# User_Interface.net
KiCad netlist of a schematic drawn in Altium Designer
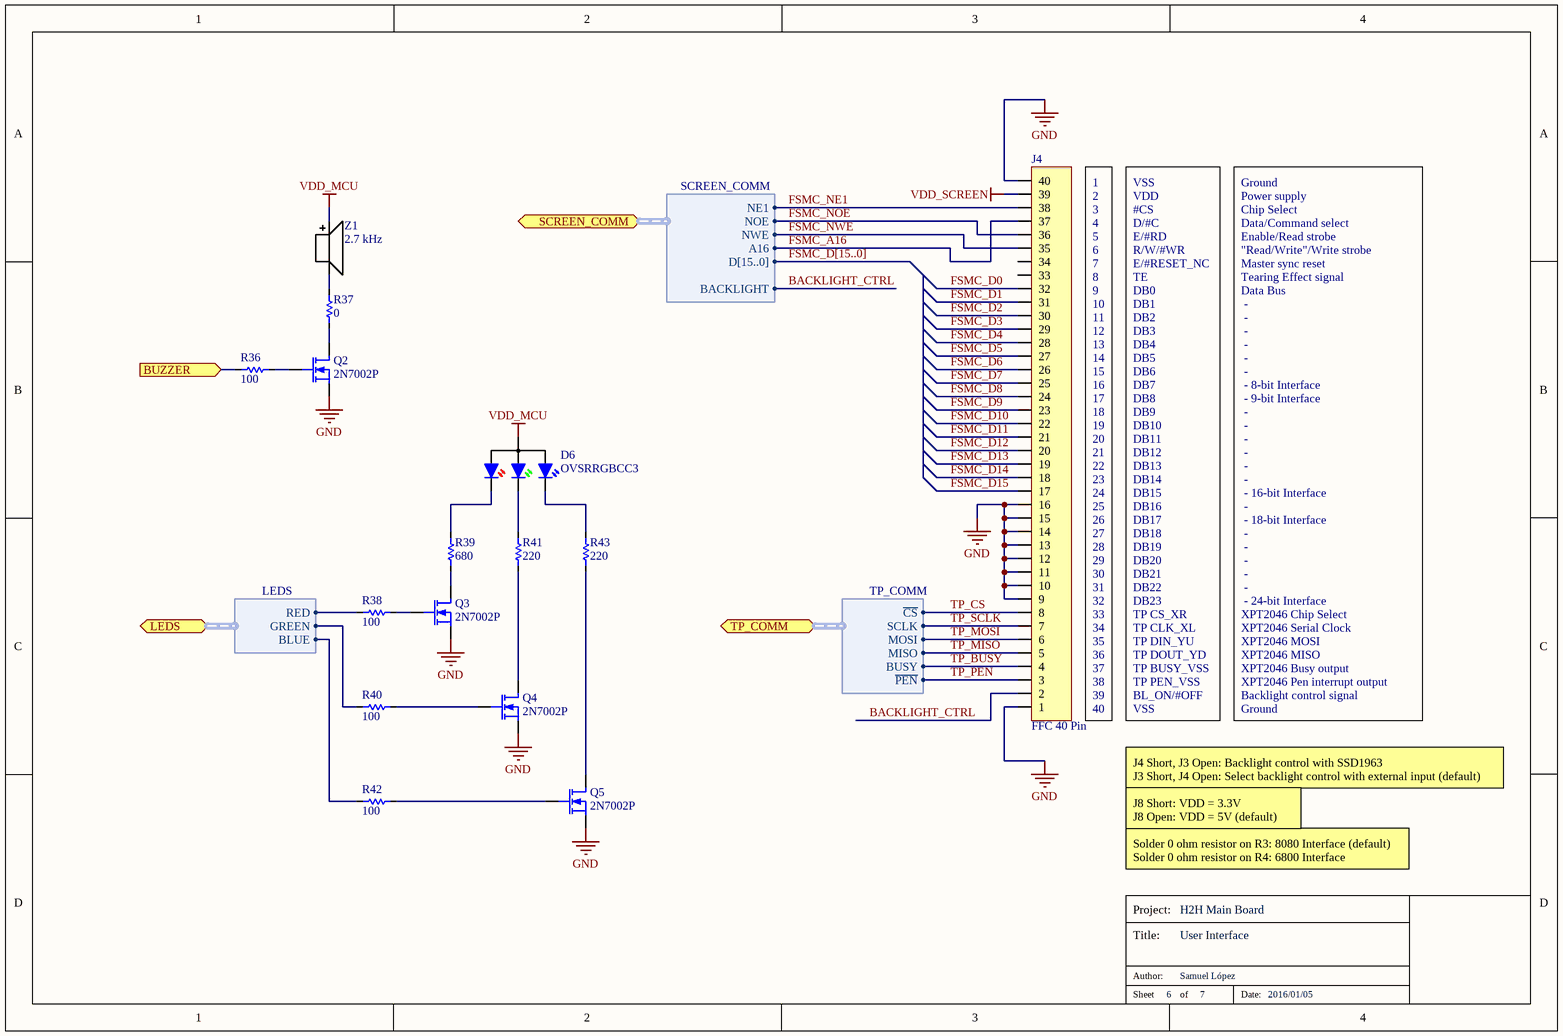
[diagram p0: User Interface.SchDoc]

(export (version "E")
  (design (tool "Eeschema 10.0.6"))
  (components
    (comp (ref "D6")
      (value "OVSRRGBCC3")
      (footprint "OVSRRGBCC3/SIDE")
      (description "LED - RGB, Top/Side-emmiting")
      (libsource (lib "H2H") (part "OVSRRGBCC3"))
    )
    (comp (ref "J4")
      (value "FFC 40 Pin")
      (footprint "ER-CON40HB-2")
      (description "Conn - FFC/FPC, 40 Pin, 1.0mm Pitch, ZIF")
      (libsource (lib "Conn") (part "ER-CON40HB-2"))
    )
    (comp (ref "Q2")
      (value "2N7002P")
      (footprint "2N7002P")
      (description "Transistor - MOSFET, N-Channel, 60V, 300mA")
      (libsource (lib "H2H") (part "2N7002P"))
    )
    (comp (ref "Q3")
      (value "2N7002P")
      (footprint "2N7002P")
      (description "Transistor - MOSFET, N-Channel, 60V, 300mA")
      (libsource (lib "H2H") (part "2N7002P"))
    )
    (comp (ref "Q4")
      (value "2N7002P")
      (footprint "2N7002P")
      (description "Transistor - MOSFET, N-Channel, 60V, 300mA")
      (libsource (lib "H2H") (part "2N7002P"))
    )
    (comp (ref "Q5")
      (value "2N7002P")
      (footprint "2N7002P")
      (description "Transistor - MOSFET, N-Channel, 60V, 300mA")
      (libsource (lib "H2H") (part "2N7002P"))
    )
    (comp (ref "R36")
      (value "100")
      (footprint "R0603")
      (description "Resistor")
      (libsource (lib "Misc") (part "Resistor"))
    )
    (comp (ref "R37")
      (value "0")
      (footprint "R0603")
      (description "Resistor")
      (libsource (lib "Misc") (part "Resistor"))
    )
    (comp (ref "R38")
      (value "100")
      (footprint "R0603")
      (description "Resistor")
      (libsource (lib "Misc") (part "Resistor"))
    )
    (comp (ref "R39")
      (value "680")
      (footprint "R0603")
      (description "Resistor")
      (libsource (lib "Misc") (part "Resistor"))
    )
    (comp (ref "R40")
      (value "100")
      (footprint "R0603")
      (description "Resistor")
      (libsource (lib "Misc") (part "Resistor"))
    )
    (comp (ref "R41")
      (value "220")
      (footprint "R0603")
      (description "Resistor")
      (libsource (lib "Misc") (part "Resistor"))
    )
    (comp (ref "R42")
      (value "100")
      (footprint "R0603")
      (description "Resistor")
      (libsource (lib "Misc") (part "Resistor"))
    )
    (comp (ref "R43")
      (value "220")
      (footprint "R0603")
      (description "Resistor")
      (libsource (lib "Misc") (part "Resistor"))
    )
    (comp (ref "Z1")
      (value "2.7 kHz")
      (footprint "KSSG74B16")
      (description "Transductor - Buzzer 2.7 kHz")
      (libsource (lib "H2H") (part "KSSG74B16"))
    )
  )
  (nets
    (net (code "4") (name "/BACKLIGHT_CTRL") (class "Default")
      (node (ref "J4") (pin "2") (pinfunction "2_2") (pintype "passive"))
    )
    (net (code "5") (name "/BLUE") (class "Default")
      (node (ref "R42") (pin "2") (pinfunction "2_2") (pintype "passive"))
    )
    (net (code "6") (name "/BUZZER") (class "Default")
      (node (ref "R36") (pin "1") (pinfunction "1_1") (pintype "passive"))
    )
    (net (code "7") (name "/FSMC_A16") (class "Default")
      (node (ref "J4") (pin "37") (pinfunction "37_37") (pintype "passive"))
    )
    (net (code "8") (name "/FSMC_D0") (class "Default")
      (node (ref "J4") (pin "32") (pinfunction "32_32") (pintype "passive"))
    )
    (net (code "9") (name "/FSMC_D1") (class "Default")
      (node (ref "J4") (pin "31") (pinfunction "31_31") (pintype "passive"))
    )
    (net (code "10") (name "/FSMC_D2") (class "Default")
      (node (ref "J4") (pin "30") (pinfunction "30_30") (pintype "passive"))
    )
    (net (code "11") (name "/FSMC_D3") (class "Default")
      (node (ref "J4") (pin "29") (pinfunction "29_29") (pintype "passive"))
    )
    (net (code "12") (name "/FSMC_D4") (class "Default")
      (node (ref "J4") (pin "28") (pinfunction "28_28") (pintype "passive"))
    )
    (net (code "13") (name "/FSMC_D5") (class "Default")
      (node (ref "J4") (pin "27") (pinfunction "27_27") (pintype "passive"))
    )
    (net (code "14") (name "/FSMC_D6") (class "Default")
      (node (ref "J4") (pin "26") (pinfunction "26_26") (pintype "passive"))
    )
    (net (code "15") (name "/FSMC_D7") (class "Default")
      (node (ref "J4") (pin "25") (pinfunction "25_25") (pintype "passive"))
    )
    (net (code "16") (name "/FSMC_D8") (class "Default")
      (node (ref "J4") (pin "24") (pinfunction "24_24") (pintype "passive"))
    )
    (net (code "17") (name "/FSMC_D9") (class "Default")
      (node (ref "J4") (pin "23") (pinfunction "23_23") (pintype "passive"))
    )
    (net (code "18") (name "/FSMC_D10") (class "Default")
      (node (ref "J4") (pin "22") (pinfunction "22_22") (pintype "passive"))
    )
    (net (code "19") (name "/FSMC_D11") (class "Default")
      (node (ref "J4") (pin "21") (pinfunction "21_21") (pintype "passive"))
    )
    (net (code "20") (name "/FSMC_D12") (class "Default")
      (node (ref "J4") (pin "20") (pinfunction "20_20") (pintype "passive"))
    )
    (net (code "21") (name "/FSMC_D13") (class "Default")
      (node (ref "J4") (pin "19") (pinfunction "19_19") (pintype "passive"))
    )
    (net (code "22") (name "/FSMC_D14") (class "Default")
      (node (ref "J4") (pin "18") (pinfunction "18_18") (pintype "passive"))
    )
    (net (code "23") (name "/FSMC_D15") (class "Default")
      (node (ref "J4") (pin "17") (pinfunction "17_17") (pintype "passive"))
    )
    (net (code "24") (name "/FSMC_NE1") (class "Default")
      (node (ref "J4") (pin "38") (pinfunction "38_38") (pintype "passive"))
    )
    (net (code "25") (name "/FSMC_NOE") (class "Default")
      (node (ref "J4") (pin "36") (pinfunction "36_36") (pintype "passive"))
    )
    (net (code "26") (name "/FSMC_NWE") (class "Default")
      (node (ref "J4") (pin "35") (pinfunction "35_35") (pintype "passive"))
    )
    (net (code "27") (name "/GREEN") (class "Default")
      (node (ref "R40") (pin "1") (pinfunction "1_1") (pintype "passive"))
    )
    (net (code "28") (name "/RED") (class "Default")
      (node (ref "R38") (pin "1") (pinfunction "1_1") (pintype "passive"))
    )
    (net (code "30") (name "/TP_BUSY") (class "Default")
      (node (ref "J4") (pin "4") (pinfunction "4_4") (pintype "passive"))
    )
    (net (code "31") (name "/TP_CS") (class "Default")
      (node (ref "J4") (pin "8") (pinfunction "8_8") (pintype "passive"))
    )
    (net (code "32") (name "/TP_MISO") (class "Default")
      (node (ref "J4") (pin "5") (pinfunction "5_5") (pintype "passive"))
    )
    (net (code "33") (name "/TP_MOSI") (class "Default")
      (node (ref "J4") (pin "6") (pinfunction "6_6") (pintype "passive"))
    )
    (net (code "34") (name "/TP_PEN") (class "Default")
      (node (ref "J4") (pin "3") (pinfunction "3_3") (pintype "passive"))
    )
    (net (code "35") (name "/TP_SCLK") (class "Default")
      (node (ref "J4") (pin "7") (pinfunction "7_7") (pintype "passive"))
    )
    (net (code "39") (name "GND") (class "Default")
      (node (ref "J4") (pin "1") (pinfunction "1_1") (pintype "passive"))
      (node (ref "J4") (pin "10") (pinfunction "10_10") (pintype "passive"))
      (node (ref "J4") (pin "11") (pinfunction "11_11") (pintype "passive"))
      (node (ref "J4") (pin "12") (pinfunction "12_12") (pintype "passive"))
      (node (ref "J4") (pin "13") (pinfunction "13_13") (pintype "passive"))
      (node (ref "J4") (pin "14") (pinfunction "14_14") (pintype "passive"))
      (node (ref "J4") (pin "15") (pinfunction "15_15") (pintype "passive"))
      (node (ref "J4") (pin "16") (pinfunction "16_16") (pintype "passive"))
      (node (ref "J4") (pin "40") (pinfunction "40_40") (pintype "passive"))
      (node (ref "J4") (pin "9") (pinfunction "9_9") (pintype "passive"))
      (node (ref "Q2") (pin "2") (pinfunction "S_2") (pintype "passive"))
      (node (ref "Q3") (pin "2") (pinfunction "S_2") (pintype "passive"))
      (node (ref "Q4") (pin "2") (pinfunction "S_2") (pintype "passive"))
      (node (ref "Q5") (pin "2") (pinfunction "S_2") (pintype "passive"))
    )
    (net (code "40") (name "Net-(D6-K_B)") (class "Default")
      (node (ref "D6") (pin "3") (pinfunction "K_B_3") (pintype "passive"))
      (node (ref "R43") (pin "2") (pinfunction "2_2") (pintype "passive"))
    )
    (net (code "41") (name "Net-(D6-K_G)") (class "Default")
      (node (ref "D6") (pin "2") (pinfunction "K_G_2") (pintype "passive"))
      (node (ref "R41") (pin "1") (pinfunction "1_1") (pintype "passive"))
    )
    (net (code "42") (name "Net-(D6-K_R)") (class "Default")
      (node (ref "D6") (pin "1") (pinfunction "K_R_1") (pintype "passive"))
      (node (ref "R39") (pin "2") (pinfunction "2_2") (pintype "passive"))
    )
    (net (code "43") (name "Net-(Q2-D)") (class "Default")
      (node (ref "Q2") (pin "3") (pinfunction "D_3") (pintype "passive"))
      (node (ref "R37") (pin "2") (pinfunction "2_2") (pintype "passive"))
    )
    (net (code "44") (name "Net-(Q2-G)") (class "Default")
      (node (ref "Q2") (pin "1") (pinfunction "G_1") (pintype "passive"))
      (node (ref "R36") (pin "2") (pinfunction "2_2") (pintype "passive"))
    )
    (net (code "45") (name "Net-(Q3-D)") (class "Default")
      (node (ref "Q3") (pin "3") (pinfunction "D_3") (pintype "passive"))
      (node (ref "R39") (pin "1") (pinfunction "1_1") (pintype "passive"))
    )
    (net (code "46") (name "Net-(Q3-G)") (class "Default")
      (node (ref "Q3") (pin "1") (pinfunction "G_1") (pintype "passive"))
      (node (ref "R38") (pin "2") (pinfunction "2_2") (pintype "passive"))
    )
    (net (code "47") (name "Net-(Q4-D)") (class "Default")
      (node (ref "Q4") (pin "3") (pinfunction "D_3") (pintype "passive"))
      (node (ref "R41") (pin "2") (pinfunction "2_2") (pintype "passive"))
    )
    (net (code "48") (name "Net-(Q4-G)") (class "Default")
      (node (ref "Q4") (pin "1") (pinfunction "G_1") (pintype "passive"))
      (node (ref "R40") (pin "2") (pinfunction "2_2") (pintype "passive"))
    )
    (net (code "49") (name "Net-(Q5-D)") (class "Default")
      (node (ref "Q5") (pin "3") (pinfunction "D_3") (pintype "passive"))
      (node (ref "R43") (pin "1") (pinfunction "1_1") (pintype "passive"))
    )
    (net (code "50") (name "Net-(Q5-G)") (class "Default")
      (node (ref "Q5") (pin "1") (pinfunction "G_1") (pintype "passive"))
      (node (ref "R42") (pin "1") (pinfunction "1_1") (pintype "passive"))
    )
    (net (code "51") (name "Net-(Z1--)") (class "Default")
      (node (ref "R37") (pin "1") (pinfunction "1_1") (pintype "passive"))
      (node (ref "Z1") (pin "2") (pinfunction "-_2") (pintype "passive"))
    )
    (net (code "52") (name "VDD_MCU") (class "Default")
      (node (ref "D6") (pin "4") (pinfunction "A_4") (pintype "passive"))
      (node (ref "Z1") (pin "1") (pinfunction "+_1") (pintype "passive"))
    )
    (net (code "53") (name "VDD_SCREEN") (class "Default")
      (node (ref "J4") (pin "39") (pinfunction "39_39") (pintype "passive"))
    )
    (net (code "54") (name "unconnected-(J4-Pad33)") (class "Default")
      (node (ref "J4") (pin "33") (pinfunction "33_33") (pintype "passive"))
    )
    (net (code "55") (name "unconnected-(J4-Pad34)") (class "Default")
      (node (ref "J4") (pin "34") (pinfunction "34_34") (pintype "passive"))
    )
  )
)
